# IO.net
KiCad netlist of a schematic drawn in Altium Designer
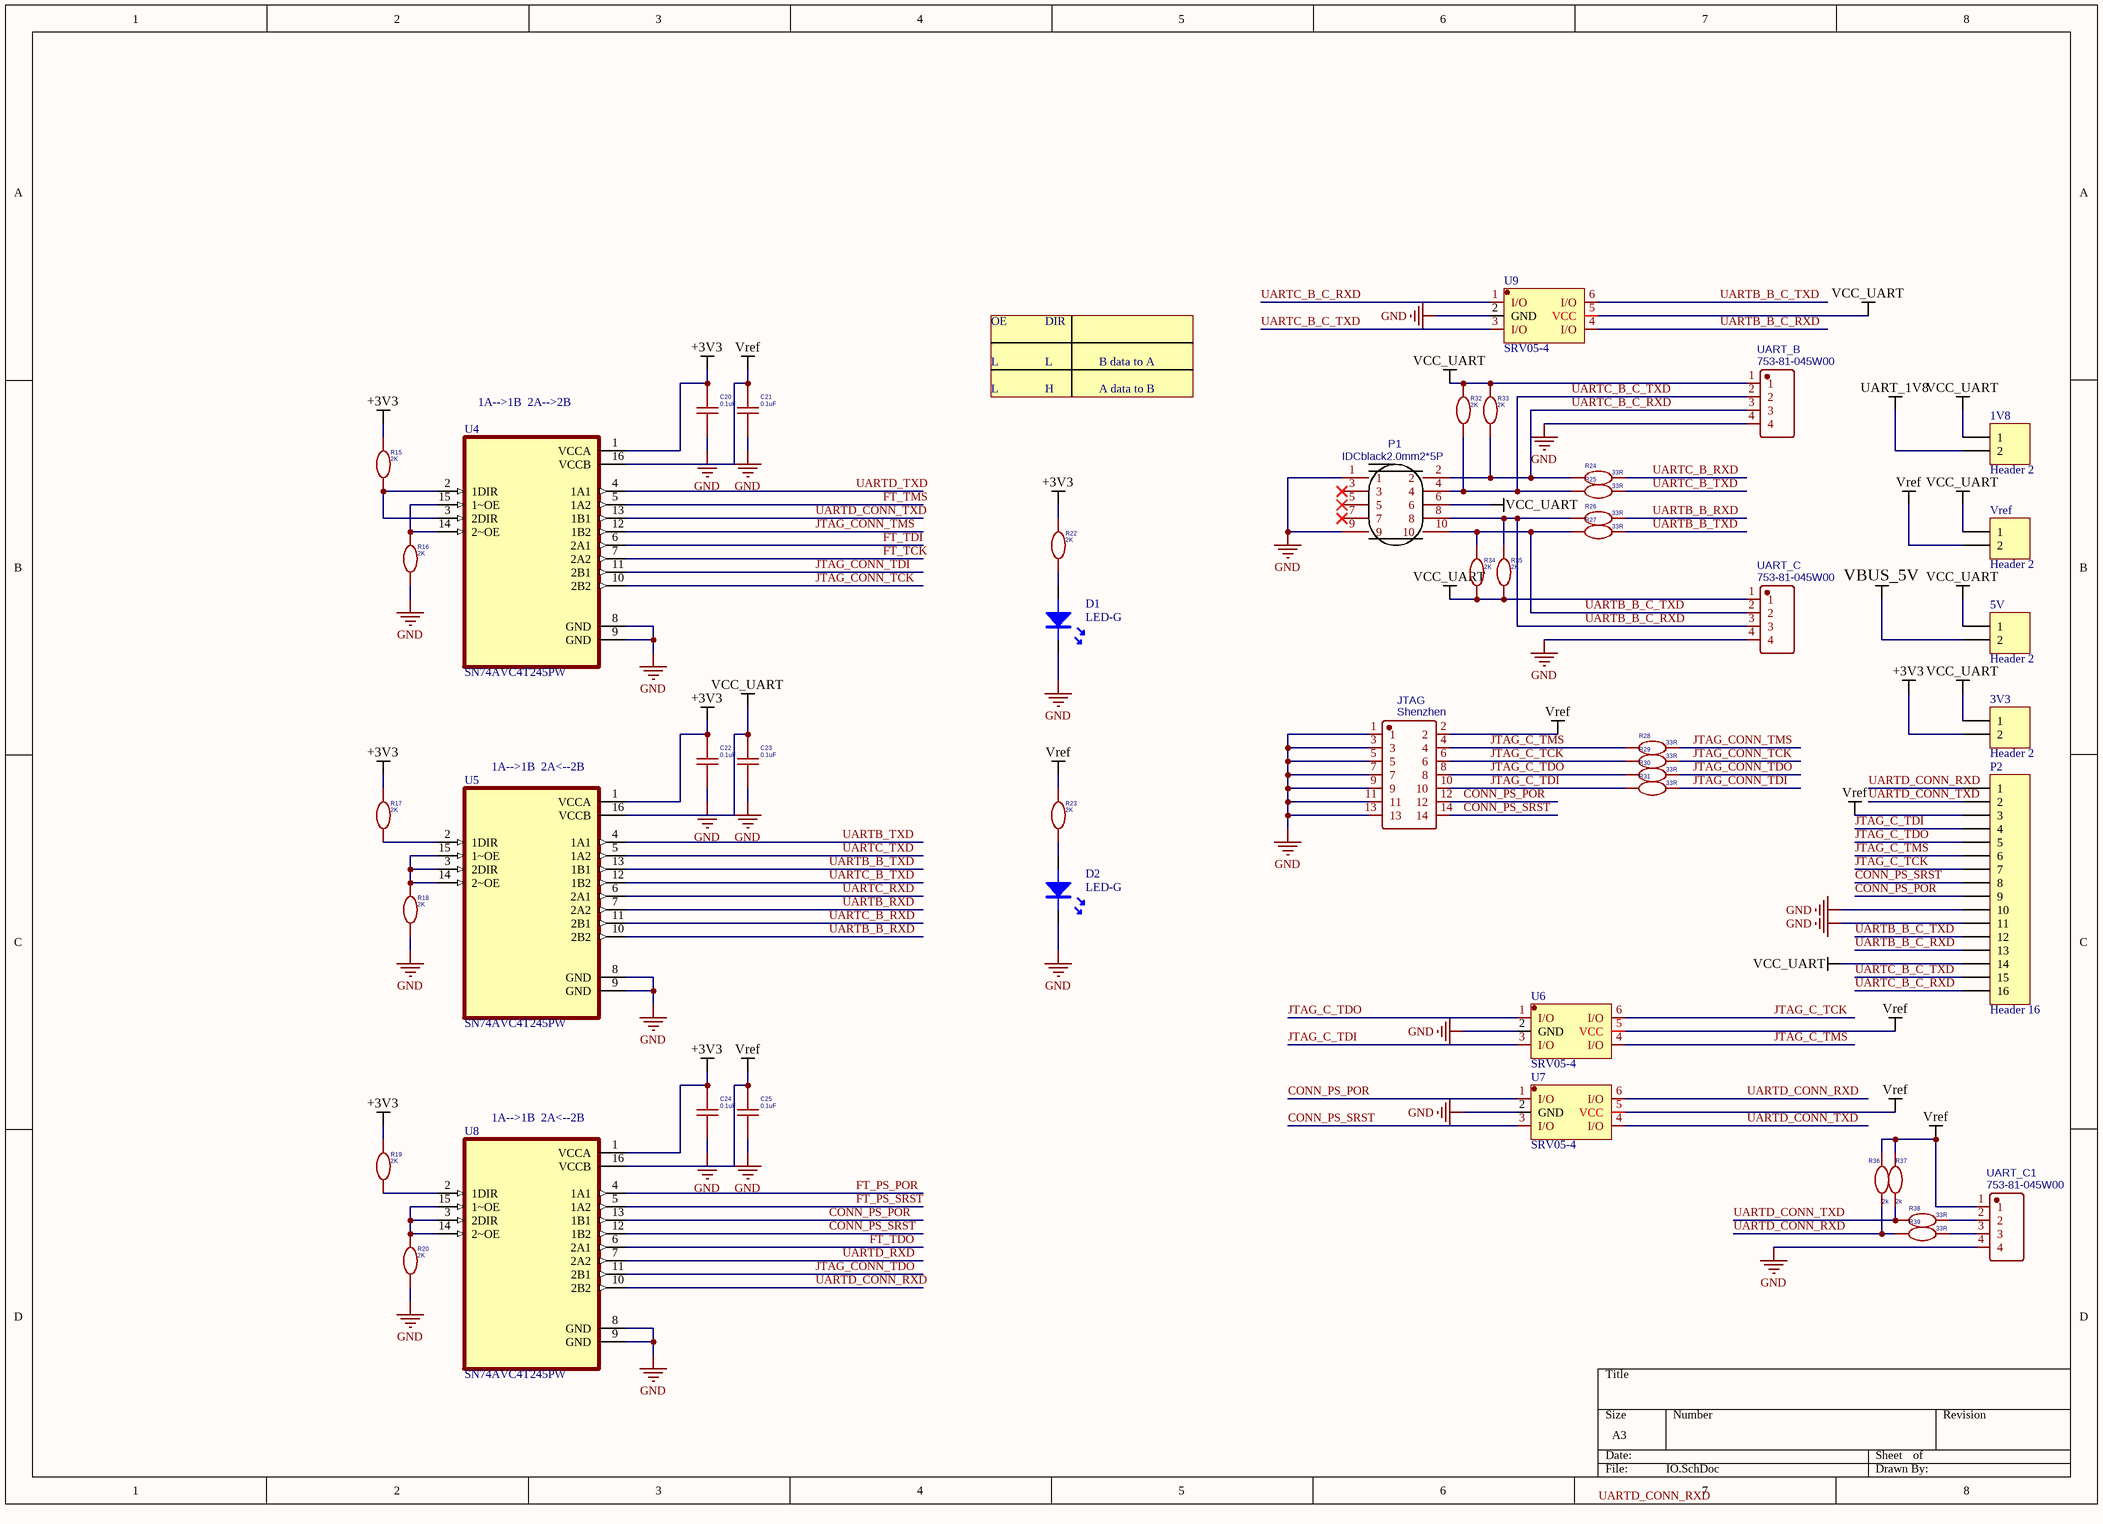
[diagram p0: IO.SchDoc]

(export (version "E")
  (design (tool "Eeschema 10.0.6"))
  (components
    (comp (ref "1V8")
      (value "Header 2")
      (footprint "HDR1X2")
      (description "Header, 2-Pin")
      (fields (field (name "PUBLISHER") "Altium Limited"))
      (libsource (lib "Miscellaneous Connectors") (part "Header 2"))
    )
    (comp (ref "3V3")
      (value "Header 2")
      (footprint "HDR1X2")
      (description "Header, 2-Pin")
      (fields (field (name "PUBLISHER") "Altium Limited"))
      (libsource (lib "Miscellaneous Connectors") (part "Header 2"))
    )
    (comp (ref "5V")
      (value "Header 2")
      (footprint "HDR1X2")
      (description "Header, 2-Pin")
      (fields (field (name "PUBLISHER") "Altium Limited"))
      (libsource (lib "Miscellaneous Connectors") (part "Header 2"))
    )
    (comp (ref "C20")
      (value "0.1uF")
      (footprint "0603C")
      (fields (field (name "CONTRIBUTOR") "LCEDA_Lib"))
      (libsource (lib "altium-import") (part "root_1_104_"))
    )
    (comp (ref "C21")
      (value "0.1uF")
      (footprint "0603C")
      (fields (field (name "CONTRIBUTOR") "LCEDA_Lib"))
      (libsource (lib "altium-import") (part "root_1_104_"))
    )
    (comp (ref "C22")
      (value "0.1uF")
      (footprint "0603C")
      (fields (field (name "CONTRIBUTOR") "LCEDA_Lib"))
      (libsource (lib "altium-import") (part "root_1_104_"))
    )
    (comp (ref "C23")
      (value "0.1uF")
      (footprint "0603C")
      (fields (field (name "CONTRIBUTOR") "LCEDA_Lib"))
      (libsource (lib "altium-import") (part "root_1_104_"))
    )
    (comp (ref "C24")
      (value "0.1uF")
      (footprint "0603C")
      (fields (field (name "CONTRIBUTOR") "LCEDA_Lib"))
      (libsource (lib "altium-import") (part "root_1_104_"))
    )
    (comp (ref "C25")
      (value "0.1uF")
      (footprint "0603C")
      (fields (field (name "CONTRIBUTOR") "LCEDA_Lib"))
      (libsource (lib "altium-import") (part "root_1_104_"))
    )
    (comp (ref "D1") (value "LED-G") (footprint "LED-0603G") (libsource (lib "LED") (part "LED")))
    (comp (ref "D2") (value "LED-G") (footprint "LED-0603G") (libsource (lib "LED") (part "LED")))
    (comp (ref "JTAG")
      (value "Shenzhen")
      (footprint "IDC-TH_14P-P2.00_B-3002R14P-0110")
      (fields
        (field (name "BOM_SUPPLIER PART") "C383616")
        (field (name "BOM_MANUFACTURER PART") "B-3002R14P-0110")
        (field (name "CONTRIBUTOR") "LCSC")
      )
      (libsource (lib "altium-import") (part "root_0_Shenzhen_"))
    )
    (comp (ref "P1")
      (value "IDCblack2.0mm2*5P")
      (footprint "IDC-TH_10P-P2.00-C33049")
      (fields
        (field (name "BOM_MANUFACTURER PART") "2.0-2*5P弯简牛")
        (field (name "BOM_SUPPLIER PART") "C33049")
      )
      (libsource (lib "altium-import") (part "root_0_IDCblack2.0mm2*5P_"))
    )
    (comp (ref "P2")
      (value "Header 16")
      (footprint "HDR1X16")
      (description "Header, 16-Pin")
      (fields (field (name "PUBLISHER") "Altium Limited"))
      (libsource (lib "Miscellaneous Connectors") (part "Header 16"))
    )
    (comp (ref "R15")
      (value "2K")
      (footprint "0603R")
      (fields (field (name "CONTRIBUTOR") "LCEDA_Lib"))
      (libsource (lib "altium-import") (part "root_1_10K_"))
    )
    (comp (ref "R16")
      (value "2K")
      (footprint "0603R")
      (fields (field (name "CONTRIBUTOR") "LCEDA_Lib"))
      (libsource (lib "altium-import") (part "root_1_10K_"))
    )
    (comp (ref "R17")
      (value "2K")
      (footprint "0603R")
      (fields (field (name "CONTRIBUTOR") "LCEDA_Lib"))
      (libsource (lib "altium-import") (part "root_1_10K_"))
    )
    (comp (ref "R18")
      (value "2K")
      (footprint "0603R")
      (fields (field (name "CONTRIBUTOR") "LCEDA_Lib"))
      (libsource (lib "altium-import") (part "root_1_10K_"))
    )
    (comp (ref "R19")
      (value "2K")
      (footprint "0603R")
      (fields (field (name "CONTRIBUTOR") "LCEDA_Lib"))
      (libsource (lib "altium-import") (part "root_1_10K_"))
    )
    (comp (ref "R20")
      (value "2K")
      (footprint "0603R")
      (fields (field (name "CONTRIBUTOR") "LCEDA_Lib"))
      (libsource (lib "altium-import") (part "root_1_10K_"))
    )
    (comp (ref "R22")
      (value "2K")
      (footprint "0603R")
      (fields (field (name "CONTRIBUTOR") "LCEDA_Lib"))
      (libsource (lib "altium-import") (part "root_1_10K_"))
    )
    (comp (ref "R23")
      (value "2K")
      (footprint "0603R")
      (fields (field (name "CONTRIBUTOR") "LCEDA_Lib"))
      (libsource (lib "altium-import") (part "root_1_10K_"))
    )
    (comp (ref "R24")
      (value "33R")
      (footprint "0603R")
      (fields (field (name "CONTRIBUTOR") "LCEDA_Lib"))
      (libsource (lib "altium-import") (part "root_2_10K_"))
    )
    (comp (ref "R25")
      (value "33R")
      (footprint "0603R")
      (fields (field (name "CONTRIBUTOR") "LCEDA_Lib"))
      (libsource (lib "altium-import") (part "root_2_10K_"))
    )
    (comp (ref "R26")
      (value "33R")
      (footprint "0603R")
      (fields (field (name "CONTRIBUTOR") "LCEDA_Lib"))
      (libsource (lib "altium-import") (part "root_2_10K_"))
    )
    (comp (ref "R27")
      (value "33R")
      (footprint "0603R")
      (fields (field (name "CONTRIBUTOR") "LCEDA_Lib"))
      (libsource (lib "altium-import") (part "root_2_10K_"))
    )
    (comp (ref "R28")
      (value "33R")
      (footprint "0603R")
      (fields (field (name "CONTRIBUTOR") "LCEDA_Lib"))
      (libsource (lib "altium-import") (part "root_2_10K_"))
    )
    (comp (ref "R29")
      (value "33R")
      (footprint "0603R")
      (fields (field (name "CONTRIBUTOR") "LCEDA_Lib"))
      (libsource (lib "altium-import") (part "root_2_10K_"))
    )
    (comp (ref "R30")
      (value "33R")
      (footprint "0603R")
      (fields (field (name "CONTRIBUTOR") "LCEDA_Lib"))
      (libsource (lib "altium-import") (part "root_2_10K_"))
    )
    (comp (ref "R31")
      (value "33R")
      (footprint "0603R")
      (fields (field (name "CONTRIBUTOR") "LCEDA_Lib"))
      (libsource (lib "altium-import") (part "root_2_10K_"))
    )
    (comp (ref "R32")
      (value "2K")
      (footprint "0603R")
      (fields (field (name "CONTRIBUTOR") "LCEDA_Lib"))
      (libsource (lib "altium-import") (part "root_1_10K_"))
    )
    (comp (ref "R33")
      (value "2K")
      (footprint "0603R")
      (fields (field (name "CONTRIBUTOR") "LCEDA_Lib"))
      (libsource (lib "altium-import") (part "root_1_10K_"))
    )
    (comp (ref "R34")
      (value "2K")
      (footprint "0603R")
      (fields (field (name "CONTRIBUTOR") "LCEDA_Lib"))
      (libsource (lib "altium-import") (part "root_1_10K_"))
    )
    (comp (ref "R35")
      (value "2K")
      (footprint "0603R")
      (fields (field (name "CONTRIBUTOR") "LCEDA_Lib"))
      (libsource (lib "altium-import") (part "root_1_10K_"))
    )
    (comp (ref "R36")
      (value "2k")
      (footprint "0603R")
      (fields (field (name "CONTRIBUTOR") "LCEDA_Lib"))
      (libsource (lib "altium-import") (part "root_3_10K_"))
    )
    (comp (ref "R37")
      (value "2k")
      (footprint "0603R")
      (fields (field (name "CONTRIBUTOR") "LCEDA_Lib"))
      (libsource (lib "altium-import") (part "root_3_10K_"))
    )
    (comp (ref "R38")
      (value "33R")
      (footprint "0603R")
      (fields (field (name "CONTRIBUTOR") "LCEDA_Lib"))
      (libsource (lib "altium-import") (part "root_2_10K_"))
    )
    (comp (ref "R39")
      (value "33R")
      (footprint "0603R")
      (fields (field (name "CONTRIBUTOR") "LCEDA_Lib"))
      (libsource (lib "altium-import") (part "root_2_10K_"))
    )
    (comp (ref "U4")
      (value "SN74AVC4T245PW")
      (footprint "SOP65P640X120-16N")
      (fields (field (name "MF") "Texas Instruments"))
      (libsource (lib "SN74AVC4T245PW") (part "SN74AVC4T245PW"))
    )
    (comp (ref "U5")
      (value "SN74AVC4T245PW")
      (footprint "SOP65P640X120-16N")
      (fields (field (name "MF") "Texas Instruments"))
      (libsource (lib "SN74AVC4T245PW") (part "SN74AVC4T245PW"))
    )
    (comp (ref "U6") (value "SRV05-4") (footprint "SOT23-6") (libsource (lib "未分类IC") (part "SRV05-4")))
    (comp (ref "U7") (value "SRV05-4") (footprint "SOT23-6") (libsource (lib "未分类IC") (part "SRV05-4")))
    (comp (ref "U8")
      (value "SN74AVC4T245PW")
      (footprint "SOP65P640X120-16N")
      (fields (field (name "MF") "Texas Instruments"))
      (libsource (lib "SN74AVC4T245PW") (part "SN74AVC4T245PW"))
    )
    (comp (ref "U9") (value "SRV05-4") (footprint "SOT23-6") (libsource (lib "未分类IC") (part "SRV05-4")))
    (comp (ref "UART_B")
      (value "753-81-045W00")
      (footprint "CONN-TH_4P-P2.50-V-M_753")
      (fields (field (name "BOM_SUPPLIER PART") "C402792") (field (name "CONTRIBUTOR") "LCSC"))
      (libsource (lib "altium-import") (part "root_0_753-81-045W00_"))
    )
    (comp (ref "UART_C")
      (value "753-81-045W00")
      (footprint "CONN-TH_4P-P2.50-V-M_753")
      (fields (field (name "BOM_SUPPLIER PART") "C402792") (field (name "CONTRIBUTOR") "LCSC"))
      (libsource (lib "altium-import") (part "root_0_753-81-045W00_"))
    )
    (comp (ref "UART_C1")
      (value "753-81-045W00")
      (footprint "CONN-TH_4P-P2.50-V-M_753")
      (fields (field (name "BOM_SUPPLIER PART") "C402792") (field (name "CONTRIBUTOR") "LCSC"))
      (libsource (lib "altium-import") (part "root_0_753-81-045W00_"))
    )
    (comp (ref "Vref")
      (value "Header 2")
      (footprint "HDR1X2")
      (description "Header, 2-Pin")
      (fields (field (name "PUBLISHER") "Altium Limited"))
      (libsource (lib "Miscellaneous Connectors") (part "Header 2"))
    )
  )
  (nets
    (net (code "1") (name "+3V3") (class "Default")
      (node (ref "3V3") (pin "2") (pinfunction "2_2") (pintype "passive"))
      (node (ref "C20") (pin "2") (pinfunction "2_2") (pintype "passive"))
      (node (ref "C22") (pin "2") (pinfunction "2_2") (pintype "passive"))
      (node (ref "C24") (pin "2") (pinfunction "2_2") (pintype "passive"))
      (node (ref "R15") (pin "2") (pinfunction "2_2") (pintype "passive"))
      (node (ref "R17") (pin "2") (pinfunction "2_2") (pintype "passive"))
      (node (ref "R19") (pin "2") (pinfunction "2_2") (pintype "passive"))
      (node (ref "R22") (pin "2") (pinfunction "2_2") (pintype "passive"))
      (node (ref "U4") (pin "1") (pinfunction "VCCA_1") (pintype "power_in"))
      (node (ref "U5") (pin "1") (pinfunction "VCCA_1") (pintype "power_in"))
      (node (ref "U8") (pin "1") (pinfunction "VCCA_1") (pintype "power_in"))
    )
    (net (code "2") (name "/CONN_PS_POR") (class "Default")
      (node (ref "JTAG") (pin "12") (pinfunction "12_12") (pintype "passive"))
      (node (ref "P2") (pin "9") (pinfunction "9_9") (pintype "passive"))
      (node (ref "U7") (pin "1") (pinfunction "I/O_1") (pintype "passive"))
      (node (ref "U8") (pin "13") (pinfunction "1B1_13") (pintype "output"))
    )
    (net (code "3") (name "/CONN_PS_SRST") (class "Default")
      (node (ref "JTAG") (pin "14") (pinfunction "14_14") (pintype "passive"))
      (node (ref "P2") (pin "8") (pinfunction "8_8") (pintype "passive"))
      (node (ref "U7") (pin "3") (pinfunction "I/O_3") (pintype "passive"))
      (node (ref "U8") (pin "12") (pinfunction "1B2_12") (pintype "output"))
    )
    (net (code "4") (name "/FT_PS_POR") (class "Default")
      (node (ref "U8") (pin "4") (pinfunction "1A1_4") (pintype "output"))
    )
    (net (code "5") (name "/FT_PS_SRST") (class "Default")
      (node (ref "U8") (pin "5") (pinfunction "1A2_5") (pintype "output"))
    )
    (net (code "6") (name "/FT_TCK") (class "Default")
      (node (ref "U4") (pin "7") (pinfunction "2A2_7") (pintype "output"))
    )
    (net (code "7") (name "/FT_TDI") (class "Default")
      (node (ref "U4") (pin "6") (pinfunction "2A1_6") (pintype "output"))
    )
    (net (code "8") (name "/FT_TDO") (class "Default")
      (node (ref "U8") (pin "6") (pinfunction "2A1_6") (pintype "output"))
    )
    (net (code "9") (name "/FT_TMS") (class "Default")
      (node (ref "U4") (pin "5") (pinfunction "1A2_5") (pintype "output"))
    )
    (net (code "10") (name "/JTAG_CONN_TCK") (class "Default")
      (node (ref "R29") (pin "1") (pinfunction "1_1") (pintype "passive"))
      (node (ref "U4") (pin "10") (pinfunction "2B2_10") (pintype "output"))
    )
    (net (code "11") (name "/JTAG_CONN_TDI") (class "Default")
      (node (ref "R31") (pin "1") (pinfunction "1_1") (pintype "passive"))
      (node (ref "U4") (pin "11") (pinfunction "2B1_11") (pintype "output"))
    )
    (net (code "12") (name "/JTAG_CONN_TDO") (class "Default")
      (node (ref "R30") (pin "1") (pinfunction "1_1") (pintype "passive"))
      (node (ref "U8") (pin "11") (pinfunction "2B1_11") (pintype "output"))
    )
    (net (code "13") (name "/JTAG_CONN_TMS") (class "Default")
      (node (ref "R28") (pin "1") (pinfunction "1_1") (pintype "passive"))
      (node (ref "U4") (pin "12") (pinfunction "1B2_12") (pintype "output"))
    )
    (net (code "14") (name "/JTAG_C_TCK") (class "Default")
      (node (ref "JTAG") (pin "6") (pinfunction "6_6") (pintype "passive"))
      (node (ref "P2") (pin "7") (pinfunction "7_7") (pintype "passive"))
      (node (ref "R29") (pin "2") (pinfunction "2_2") (pintype "passive"))
      (node (ref "U6") (pin "6") (pinfunction "I/O_6") (pintype "passive"))
    )
    (net (code "15") (name "/JTAG_C_TDI") (class "Default")
      (node (ref "JTAG") (pin "10") (pinfunction "10_10") (pintype "passive"))
      (node (ref "P2") (pin "4") (pinfunction "4_4") (pintype "passive"))
      (node (ref "R31") (pin "2") (pinfunction "2_2") (pintype "passive"))
      (node (ref "U6") (pin "3") (pinfunction "I/O_3") (pintype "passive"))
    )
    (net (code "16") (name "/JTAG_C_TDO") (class "Default")
      (node (ref "JTAG") (pin "8") (pinfunction "8_8") (pintype "passive"))
      (node (ref "P2") (pin "5") (pinfunction "5_5") (pintype "passive"))
      (node (ref "R30") (pin "2") (pinfunction "2_2") (pintype "passive"))
      (node (ref "U6") (pin "1") (pinfunction "I/O_1") (pintype "passive"))
    )
    (net (code "17") (name "/JTAG_C_TMS") (class "Default")
      (node (ref "JTAG") (pin "4") (pinfunction "4_4") (pintype "passive"))
      (node (ref "P2") (pin "6") (pinfunction "6_6") (pintype "passive"))
      (node (ref "R28") (pin "2") (pinfunction "2_2") (pintype "passive"))
      (node (ref "U6") (pin "4") (pinfunction "I/O_4") (pintype "passive"))
    )
    (net (code "18") (name "/UARTB_B_C_RXD") (class "Default")
      (node (ref "P1") (pin "8") (pinfunction "8_8") (pintype "passive"))
      (node (ref "P2") (pin "13") (pinfunction "13_13") (pintype "passive"))
      (node (ref "R26") (pin "2") (pinfunction "2_2") (pintype "passive"))
      (node (ref "R35") (pin "2") (pinfunction "2_2") (pintype "passive"))
      (node (ref "U9") (pin "4") (pinfunction "I/O_4") (pintype "passive"))
      (node (ref "UART_C") (pin "3") (pinfunction "3_3") (pintype "passive"))
    )
    (net (code "19") (name "/UARTB_B_C_TXD") (class "Default")
      (node (ref "P1") (pin "10") (pinfunction "10_10") (pintype "passive"))
      (node (ref "P2") (pin "12") (pinfunction "12_12") (pintype "passive"))
      (node (ref "R27") (pin "2") (pinfunction "2_2") (pintype "passive"))
      (node (ref "R34") (pin "2") (pinfunction "2_2") (pintype "passive"))
      (node (ref "U9") (pin "6") (pinfunction "I/O_6") (pintype "passive"))
      (node (ref "UART_C") (pin "2") (pinfunction "2_2") (pintype "passive"))
    )
    (net (code "20") (name "/UARTB_B_RXD") (class "Default")
      (node (ref "R26") (pin "1") (pinfunction "1_1") (pintype "passive"))
      (node (ref "U5") (pin "10") (pinfunction "2B2_10") (pintype "output"))
    )
    (net (code "21") (name "/UARTB_B_TXD") (class "Default")
      (node (ref "R27") (pin "1") (pinfunction "1_1") (pintype "passive"))
      (node (ref "U5") (pin "13") (pinfunction "1B1_13") (pintype "output"))
    )
    (net (code "22") (name "/UARTB_RXD") (class "Default")
      (node (ref "U5") (pin "7") (pinfunction "2A2_7") (pintype "output"))
    )
    (net (code "23") (name "/UARTB_TXD") (class "Default")
      (node (ref "U5") (pin "4") (pinfunction "1A1_4") (pintype "output"))
    )
    (net (code "24") (name "/UARTC_B_C_RXD") (class "Default")
      (node (ref "P1") (pin "2") (pinfunction "2_2") (pintype "passive"))
      (node (ref "P2") (pin "16") (pinfunction "16_16") (pintype "passive"))
      (node (ref "R24") (pin "2") (pinfunction "2_2") (pintype "passive"))
      (node (ref "R33") (pin "1") (pinfunction "1_1") (pintype "passive"))
      (node (ref "U9") (pin "1") (pinfunction "I/O_1") (pintype "passive"))
      (node (ref "UART_B") (pin "3") (pinfunction "3_3") (pintype "passive"))
    )
    (net (code "25") (name "/UARTC_B_C_TXD") (class "Default")
      (node (ref "P1") (pin "4") (pinfunction "4_4") (pintype "passive"))
      (node (ref "P2") (pin "15") (pinfunction "15_15") (pintype "passive"))
      (node (ref "R25") (pin "2") (pinfunction "2_2") (pintype "passive"))
      (node (ref "R32") (pin "1") (pinfunction "1_1") (pintype "passive"))
      (node (ref "U9") (pin "3") (pinfunction "I/O_3") (pintype "passive"))
      (node (ref "UART_B") (pin "2") (pinfunction "2_2") (pintype "passive"))
    )
    (net (code "26") (name "/UARTC_B_RXD") (class "Default")
      (node (ref "R24") (pin "1") (pinfunction "1_1") (pintype "passive"))
      (node (ref "U5") (pin "11") (pinfunction "2B1_11") (pintype "output"))
    )
    (net (code "27") (name "/UARTC_B_TXD") (class "Default")
      (node (ref "R25") (pin "1") (pinfunction "1_1") (pintype "passive"))
      (node (ref "U5") (pin "12") (pinfunction "1B2_12") (pintype "output"))
    )
    (net (code "28") (name "/UARTC_RXD") (class "Default")
      (node (ref "U5") (pin "6") (pinfunction "2A1_6") (pintype "output"))
    )
    (net (code "29") (name "/UARTC_TXD") (class "Default")
      (node (ref "U5") (pin "5") (pinfunction "1A2_5") (pintype "output"))
    )
    (net (code "30") (name "/UARTD_CONN_RXD") (class "Default")
      (node (ref "P2") (pin "1") (pinfunction "1_1") (pintype "passive"))
      (node (ref "R36") (pin "2") (pinfunction "2_2") (pintype "passive"))
      (node (ref "R39") (pin "2") (pinfunction "2_2") (pintype "passive"))
      (node (ref "U7") (pin "6") (pinfunction "I/O_6") (pintype "passive"))
      (node (ref "U8") (pin "10") (pinfunction "2B2_10") (pintype "output"))
    )
    (net (code "31") (name "/UARTD_CONN_TXD") (class "Default")
      (node (ref "P2") (pin "2") (pinfunction "2_2") (pintype "passive"))
      (node (ref "R37") (pin "2") (pinfunction "2_2") (pintype "passive"))
      (node (ref "R38") (pin "2") (pinfunction "2_2") (pintype "passive"))
      (node (ref "U4") (pin "13") (pinfunction "1B1_13") (pintype "output"))
      (node (ref "U7") (pin "4") (pinfunction "I/O_4") (pintype "passive"))
    )
    (net (code "32") (name "/UARTD_RXD") (class "Default")
      (node (ref "U8") (pin "7") (pinfunction "2A2_7") (pintype "output"))
    )
    (net (code "33") (name "/UARTD_TXD") (class "Default")
      (node (ref "U4") (pin "4") (pinfunction "1A1_4") (pintype "output"))
    )
    (net (code "34") (name "GND") (class "Default")
      (node (ref "C20") (pin "1") (pinfunction "1_1") (pintype "passive"))
      (node (ref "C21") (pin "1") (pinfunction "1_1") (pintype "passive"))
      (node (ref "C22") (pin "1") (pinfunction "1_1") (pintype "passive"))
      (node (ref "C23") (pin "1") (pinfunction "1_1") (pintype "passive"))
      (node (ref "C24") (pin "1") (pinfunction "1_1") (pintype "passive"))
      (node (ref "C25") (pin "1") (pinfunction "1_1") (pintype "passive"))
      (node (ref "D1") (pin "K") (pinfunction "K_K") (pintype "passive"))
      (node (ref "D2") (pin "K") (pinfunction "K_K") (pintype "passive"))
      (node (ref "JTAG") (pin "1") (pinfunction "1_1") (pintype "passive"))
      (node (ref "JTAG") (pin "11") (pinfunction "11_11") (pintype "passive"))
      (node (ref "JTAG") (pin "13") (pinfunction "13_13") (pintype "passive"))
      (node (ref "JTAG") (pin "3") (pinfunction "3_3") (pintype "passive"))
      (node (ref "JTAG") (pin "5") (pinfunction "5_5") (pintype "passive"))
      (node (ref "JTAG") (pin "7") (pinfunction "7_7") (pintype "passive"))
      (node (ref "JTAG") (pin "9") (pinfunction "9_9") (pintype "passive"))
      (node (ref "P1") (pin "1") (pinfunction "1_1") (pintype "passive"))
      (node (ref "P1") (pin "9") (pinfunction "9_9") (pintype "passive"))
      (node (ref "P2") (pin "10") (pinfunction "10_10") (pintype "passive"))
      (node (ref "P2") (pin "11") (pinfunction "11_11") (pintype "passive"))
      (node (ref "R16") (pin "1") (pinfunction "1_1") (pintype "passive"))
      (node (ref "R18") (pin "1") (pinfunction "1_1") (pintype "passive"))
      (node (ref "R20") (pin "1") (pinfunction "1_1") (pintype "passive"))
      (node (ref "U4") (pin "8") (pinfunction "GND_8") (pintype "power_in"))
      (node (ref "U4") (pin "9") (pinfunction "GND_9") (pintype "power_in"))
      (node (ref "U5") (pin "8") (pinfunction "GND_8") (pintype "power_in"))
      (node (ref "U5") (pin "9") (pinfunction "GND_9") (pintype "power_in"))
      (node (ref "U6") (pin "2") (pinfunction "GND_2") (pintype "passive"))
      (node (ref "U7") (pin "2") (pinfunction "GND_2") (pintype "passive"))
      (node (ref "U8") (pin "8") (pinfunction "GND_8") (pintype "power_in"))
      (node (ref "U8") (pin "9") (pinfunction "GND_9") (pintype "power_in"))
      (node (ref "U9") (pin "2") (pinfunction "GND_2") (pintype "passive"))
      (node (ref "UART_B") (pin "4") (pinfunction "4_4") (pintype "passive"))
      (node (ref "UART_C") (pin "4") (pinfunction "4_4") (pintype "passive"))
      (node (ref "UART_C1") (pin "4") (pinfunction "4_4") (pintype "passive"))
    )
    (net (code "35") (name "Net-(D1-PadA)") (class "Default")
      (node (ref "D1") (pin "A") (pinfunction "A_A") (pintype "passive"))
      (node (ref "R22") (pin "1") (pinfunction "1_1") (pintype "passive"))
    )
    (net (code "36") (name "Net-(D2-PadA)") (class "Default")
      (node (ref "D2") (pin "A") (pinfunction "A_A") (pintype "passive"))
      (node (ref "R23") (pin "1") (pinfunction "1_1") (pintype "passive"))
    )
    (net (code "37") (name "Net-(R38-Pad1)") (class "Default")
      (node (ref "R38") (pin "1") (pinfunction "1_1") (pintype "passive"))
      (node (ref "UART_C1") (pin "2") (pinfunction "2_2") (pintype "passive"))
    )
    (net (code "38") (name "Net-(R39-Pad1)") (class "Default")
      (node (ref "R39") (pin "1") (pinfunction "1_1") (pintype "passive"))
      (node (ref "UART_C1") (pin "3") (pinfunction "3_3") (pintype "passive"))
    )
    (net (code "39") (name "Net-(U4-1DIR)") (class "Default")
      (node (ref "R15") (pin "1") (pinfunction "1_1") (pintype "passive"))
      (node (ref "U4") (pin "2") (pinfunction "1DIR_2") (pintype "input"))
      (node (ref "U4") (pin "3") (pinfunction "2DIR_3") (pintype "input"))
    )
    (net (code "40") (name "Net-(U4-1~OE)") (class "Default")
      (node (ref "R16") (pin "2") (pinfunction "2_2") (pintype "passive"))
      (node (ref "U4") (pin "14") (pinfunction "2~OE_14") (pintype "input"))
      (node (ref "U4") (pin "15") (pinfunction "1~OE_15") (pintype "input"))
    )
    (net (code "41") (name "Net-(U5-1DIR)") (class "Default")
      (node (ref "R17") (pin "1") (pinfunction "1_1") (pintype "passive"))
      (node (ref "U5") (pin "2") (pinfunction "1DIR_2") (pintype "input"))
    )
    (net (code "42") (name "Net-(U5-1~OE)") (class "Default")
      (node (ref "R18") (pin "2") (pinfunction "2_2") (pintype "passive"))
      (node (ref "U5") (pin "14") (pinfunction "2~OE_14") (pintype "input"))
      (node (ref "U5") (pin "15") (pinfunction "1~OE_15") (pintype "input"))
      (node (ref "U5") (pin "3") (pinfunction "2DIR_3") (pintype "input"))
    )
    (net (code "43") (name "Net-(U8-1DIR)") (class "Default")
      (node (ref "R19") (pin "1") (pinfunction "1_1") (pintype "passive"))
      (node (ref "U8") (pin "2") (pinfunction "1DIR_2") (pintype "input"))
    )
    (net (code "44") (name "Net-(U8-1~OE)") (class "Default")
      (node (ref "R20") (pin "2") (pinfunction "2_2") (pintype "passive"))
      (node (ref "U8") (pin "14") (pinfunction "2~OE_14") (pintype "input"))
      (node (ref "U8") (pin "15") (pinfunction "1~OE_15") (pintype "input"))
      (node (ref "U8") (pin "3") (pinfunction "2DIR_3") (pintype "input"))
    )
    (net (code "45") (name "UART_1V8") (class "Default")
      (node (ref "1V8") (pin "2") (pinfunction "2_2") (pintype "passive"))
    )
    (net (code "46") (name "VBUS_5V") (class "Default")
      (node (ref "5V") (pin "2") (pinfunction "2_2") (pintype "passive"))
    )
    (net (code "47") (name "VCC_UART") (class "Default")
      (node (ref "1V8") (pin "1") (pinfunction "1_1") (pintype "passive"))
      (node (ref "3V3") (pin "1") (pinfunction "1_1") (pintype "passive"))
      (node (ref "5V") (pin "1") (pinfunction "1_1") (pintype "passive"))
      (node (ref "C23") (pin "2") (pinfunction "2_2") (pintype "passive"))
      (node (ref "P1") (pin "6") (pinfunction "6_6") (pintype "passive"))
      (node (ref "P2") (pin "14") (pinfunction "14_14") (pintype "passive"))
      (node (ref "R32") (pin "2") (pinfunction "2_2") (pintype "passive"))
      (node (ref "R33") (pin "2") (pinfunction "2_2") (pintype "passive"))
      (node (ref "R34") (pin "1") (pinfunction "1_1") (pintype "passive"))
      (node (ref "R35") (pin "1") (pinfunction "1_1") (pintype "passive"))
      (node (ref "U5") (pin "16") (pinfunction "VCCB_16") (pintype "power_in"))
      (node (ref "U9") (pin "5") (pinfunction "VCC_5") (pintype "passive"))
      (node (ref "UART_B") (pin "1") (pinfunction "1_1") (pintype "passive"))
      (node (ref "UART_C") (pin "1") (pinfunction "1_1") (pintype "passive"))
      (node (ref "Vref") (pin "1") (pinfunction "1_1") (pintype "passive"))
    )
    (net (code "48") (name "Vref") (class "Default")
      (node (ref "C21") (pin "2") (pinfunction "2_2") (pintype "passive"))
      (node (ref "C25") (pin "2") (pinfunction "2_2") (pintype "passive"))
      (node (ref "JTAG") (pin "2") (pinfunction "2_2") (pintype "passive"))
      (node (ref "P2") (pin "3") (pinfunction "3_3") (pintype "passive"))
      (node (ref "R23") (pin "2") (pinfunction "2_2") (pintype "passive"))
      (node (ref "R36") (pin "1") (pinfunction "1_1") (pintype "passive"))
      (node (ref "R37") (pin "1") (pinfunction "1_1") (pintype "passive"))
      (node (ref "U4") (pin "16") (pinfunction "VCCB_16") (pintype "power_in"))
      (node (ref "U6") (pin "5") (pinfunction "VCC_5") (pintype "passive"))
      (node (ref "U7") (pin "5") (pinfunction "VCC_5") (pintype "passive"))
      (node (ref "U8") (pin "16") (pinfunction "VCCB_16") (pintype "power_in"))
      (node (ref "UART_C1") (pin "1") (pinfunction "1_1") (pintype "passive"))
      (node (ref "Vref") (pin "2") (pinfunction "2_2") (pintype "passive"))
    )
    (net (code "49") (name "unconnected-(P1-Pad3)") (class "Default")
      (node (ref "P1") (pin "3") (pinfunction "3_3") (pintype "passive+no_connect"))
    )
    (net (code "50") (name "unconnected-(P1-Pad5)") (class "Default")
      (node (ref "P1") (pin "5") (pinfunction "5_5") (pintype "passive+no_connect"))
    )
    (net (code "51") (name "unconnected-(P1-Pad7)") (class "Default")
      (node (ref "P1") (pin "7") (pinfunction "7_7") (pintype "passive+no_connect"))
    )
  )
)
